# main.net
KiCad netlist of a schematic drawn in EAGLE
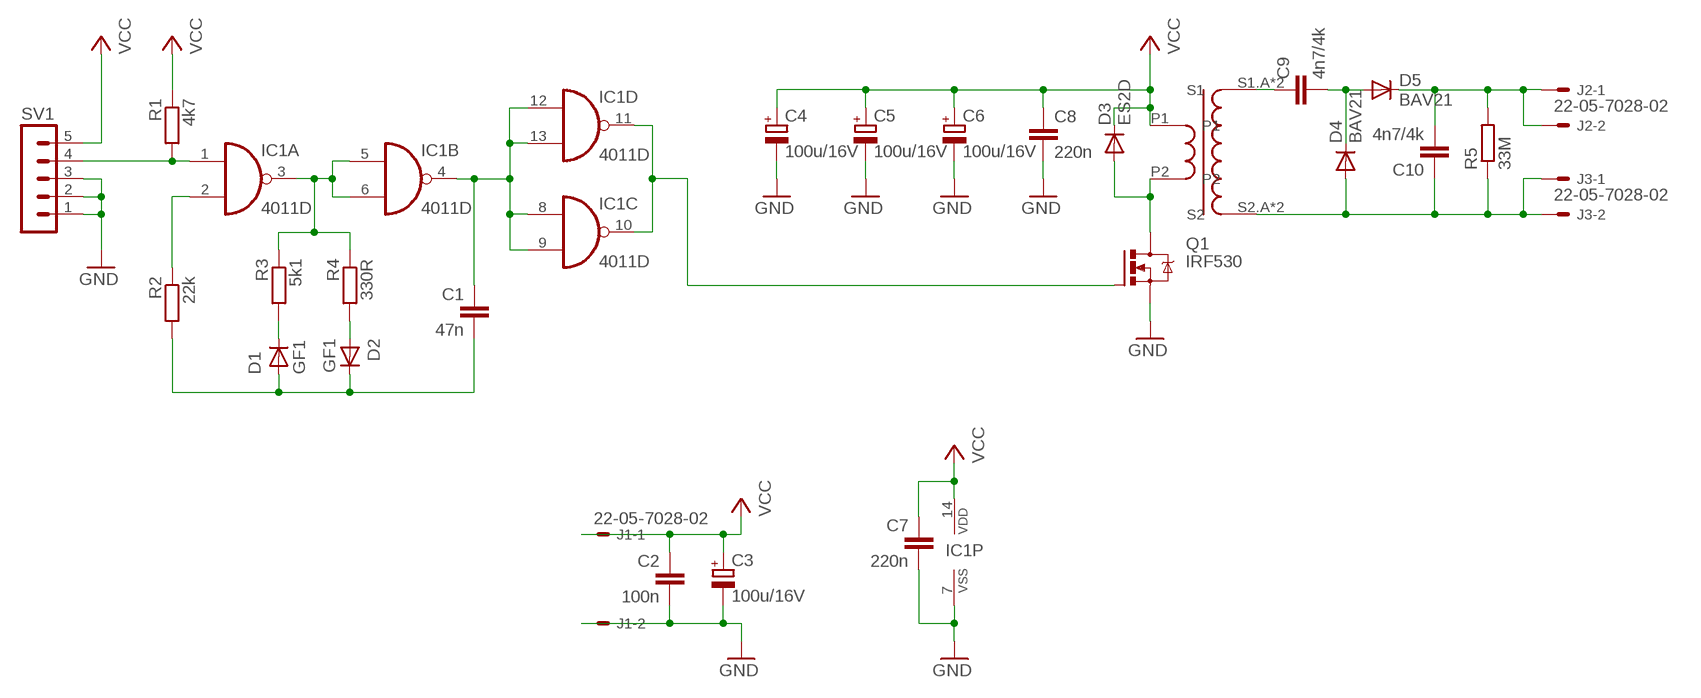
[diagram p0: schematic, sheet 1]

(export (version "E")
  (design (tool "Eeschema 10.0.6"))
  (components
    (comp (ref "11")
      (value "CCFL_INVERTER_COIL")
      (footprint "eagle-import:CCFL_INVERTER_COIL")
      (libsource (lib "eagle-import") (part "CCFL_INVERTER_COIL"))
    )
    (comp (ref "C1")
      (value "47n")
      (footprint "eagle-import:C025-025X050")
      (libsource (lib "eagle-import") (part "resistor_C-EU025-025X050"))
    )
    (comp (ref "C2")
      (value "100n")
      (footprint "eagle-import:C0805")
      (libsource (lib "eagle-import") (part "resistor_C-EUC0805"))
    )
    (comp (ref "C3")
      (value "100u/16V")
      (footprint "eagle-import:153CLV-0505")
      (libsource (lib "eagle-import") (part "CPOL-EU153CLV-0505"))
    )
    (comp (ref "C4")
      (value "100u/16V")
      (footprint "eagle-import:153CLV-0505")
      (libsource (lib "eagle-import") (part "CPOL-EU153CLV-0505"))
    )
    (comp (ref "C5")
      (value "100u/16V")
      (footprint "eagle-import:153CLV-0505")
      (libsource (lib "eagle-import") (part "resistor_CPOL-EU153CLV-0505"))
    )
    (comp (ref "C6")
      (value "100u/16V")
      (footprint "eagle-import:153CLV-0505")
      (libsource (lib "eagle-import") (part "CPOL-EU153CLV-0505"))
    )
    (comp (ref "C7")
      (value "220n")
      (footprint "eagle-import:C0805")
      (libsource (lib "eagle-import") (part "resistor_C-EUC0805"))
    )
    (comp (ref "C8")
      (value "220n")
      (footprint "eagle-import:C0805")
      (libsource (lib "eagle-import") (part "resistor_C-EUC0805"))
    )
    (comp (ref "C9")
      (value "4n7/4k")
      (footprint "eagle-import:C075-042X103")
      (libsource (lib "eagle-import") (part "C-EU075-042X103"))
    )
    (comp (ref "C10")
      (value "4n7/4k")
      (footprint "eagle-import:C075-042X103")
      (libsource (lib "eagle-import") (part "resistor_C-EU075-042X103"))
    )
    (comp (ref "D1")
      (value "GF1")
      (footprint "eagle-import:SMA-DO214AC")
      (libsource (lib "eagle-import") (part "GF1"))
    )
    (comp (ref "D2")
      (value "GF1")
      (footprint "eagle-import:SMA-DO214AC")
      (libsource (lib "eagle-import") (part "GF1"))
    )
    (comp (ref "D3")
      (value "ES2D")
      (footprint "eagle-import:SMB")
      (libsource (lib "eagle-import") (part "ES2D"))
    )
    (comp (ref "D4")
      (value "BAV21")
      (footprint "eagle-import:DO35-10")
      (libsource (lib "eagle-import") (part "BAV21"))
    )
    (comp (ref "D5")
      (value "BAV21")
      (footprint "eagle-import:DO35-10")
      (libsource (lib "eagle-import") (part "BAV21"))
    )
    (comp (ref "IC1")
      (value "4011D")
      (footprint "eagle-import:SO14")
      (libsource (lib "eagle-import") (part "4011D"))
    )
    (comp (ref "J1")
      (value "22-05-7028-02")
      (footprint "eagle-import:7395-02")
      (libsource (lib "eagle-import") (part "22-?-0205-7028"))
    )
    (comp (ref "J2")
      (value "22-05-7028-02")
      (footprint "eagle-import:7395-02")
      (libsource (lib "eagle-import") (part "22-?-0205-7028"))
    )
    (comp (ref "J3")
      (value "22-05-7028-02")
      (footprint "eagle-import:7395-02")
      (libsource (lib "eagle-import") (part "22-?-0205-7028"))
    )
    (comp (ref "Q1")
      (value "IRF530")
      (footprint "eagle-import:TO220BV")
      (libsource (lib "eagle-import") (part "IRF530"))
    )
    (comp (ref "R1")
      (value "4k7")
      (footprint "eagle-import:M0805")
      (libsource (lib "eagle-import") (part "R-EU_M0805"))
    )
    (comp (ref "R2")
      (value "22k")
      (footprint "eagle-import:M0805")
      (libsource (lib "eagle-import") (part "R-EU_M0805"))
    )
    (comp (ref "R3")
      (value "5k1")
      (footprint "eagle-import:M0805")
      (libsource (lib "eagle-import") (part "R-EU_M0805"))
    )
    (comp (ref "R4")
      (value "330R")
      (footprint "eagle-import:M0805")
      (libsource (lib "eagle-import") (part "R-EU_M0805"))
    )
    (comp (ref "R5")
      (value "33M")
      (footprint "eagle-import:0207_10")
      (libsource (lib "eagle-import") (part "R-EU_0207/10"))
    )
    (comp (ref "SV1")
      (value "MA05-1")
      (footprint "eagle-import:MA05-1")
      (libsource (lib "eagle-import") (part "MA05-1"))
    )
  )
  (nets
    (net (code "1") (name "GND") (class "Default")
      (node (ref "C2") (pin "2") (pinfunction "2_2") (pintype "passive"))
      (node (ref "C3") (pin "-") (pinfunction "-_-") (pintype "passive"))
      (node (ref "C4") (pin "-") (pinfunction "-_-") (pintype "passive"))
      (node (ref "C5") (pin "-") (pinfunction "-_-") (pintype "passive"))
      (node (ref "C6") (pin "-") (pinfunction "-_-") (pintype "passive"))
      (node (ref "C7") (pin "2") (pinfunction "2_2") (pintype "passive"))
      (node (ref "C8") (pin "2") (pinfunction "2_2") (pintype "passive"))
      (node (ref "IC1") (pin "7") (pinfunction "VSS_7") (pintype "power_in"))
      (node (ref "J1") (pin "2") (pinfunction "S_2") (pintype "passive"))
      (node (ref "Q1") (pin "S") (pinfunction "S_S") (pintype "passive"))
      (node (ref "SV1") (pin "1") (pinfunction "1_1") (pintype "passive"))
      (node (ref "SV1") (pin "2") (pinfunction "2_2") (pintype "passive"))
      (node (ref "SV1") (pin "3") (pinfunction "3_3") (pintype "passive"))
    )
    (net (code "2") (name "Net-(11-PadP2)") (class "Default")
      (node (ref "11") (pin "P2") (pinfunction "P2_P2") (pintype "input"))
      (node (ref "D3") (pin "A") (pinfunction "A_A") (pintype "passive"))
      (node (ref "Q1") (pin "D") (pinfunction "D_D") (pintype "passive"))
    )
    (net (code "3") (name "Net-(11-S1-PadS1.A)") (class "Default")
      (node (ref "11") (pin "S1.A") (pinfunction "S1_S1.A") (pintype "output"))
      (node (ref "11") (pin "S1.B") (pinfunction "S1_S1.B") (pintype "output"))
      (node (ref "C9") (pin "1") (pinfunction "1_1") (pintype "passive"))
    )
    (net (code "4") (name "Net-(C9-Pad2)") (class "Default")
      (node (ref "C9") (pin "2") (pinfunction "2_2") (pintype "passive"))
      (node (ref "D4") (pin "C") (pinfunction "C_C") (pintype "passive"))
      (node (ref "D5") (pin "A") (pinfunction "A_A") (pintype "passive"))
    )
    (net (code "5") (name "Net-(D1-C)") (class "Default")
      (node (ref "D1") (pin "K") (pinfunction "C_K") (pintype "passive"))
      (node (ref "R3") (pin "2") (pinfunction "2_2") (pintype "passive"))
    )
    (net (code "6") (name "Net-(D2-C)") (class "Default")
      (node (ref "C1") (pin "2") (pinfunction "2_2") (pintype "passive"))
      (node (ref "D1") (pin "A") (pinfunction "A_A") (pintype "passive"))
      (node (ref "D2") (pin "K") (pinfunction "C_K") (pintype "passive"))
      (node (ref "R2") (pin "2") (pinfunction "2_2") (pintype "passive"))
    )
    (net (code "7") (name "Net-(D2-PadA)") (class "Default")
      (node (ref "D2") (pin "A") (pinfunction "A_A") (pintype "passive"))
      (node (ref "R4") (pin "2") (pinfunction "2_2") (pintype "passive"))
    )
    (net (code "8") (name "Net-(IC1A-I0)") (class "Default")
      (node (ref "IC1") (pin "1") (pinfunction "I0_1") (pintype "input"))
      (node (ref "R1") (pin "2") (pinfunction "2_2") (pintype "passive"))
      (node (ref "SV1") (pin "4") (pinfunction "4_4") (pintype "passive"))
    )
    (net (code "9") (name "Net-(IC1A-I1)") (class "Default")
      (node (ref "IC1") (pin "2") (pinfunction "I1_2") (pintype "input"))
      (node (ref "R2") (pin "1") (pinfunction "1_1") (pintype "passive"))
    )
    (net (code "10") (name "Net-(IC1A-O)") (class "Default")
      (node (ref "IC1") (pin "3") (pinfunction "O_3") (pintype "output"))
      (node (ref "IC1") (pin "5") (pinfunction "I0_5") (pintype "input"))
      (node (ref "IC1") (pin "6") (pinfunction "I1_6") (pintype "input"))
      (node (ref "R3") (pin "1") (pinfunction "1_1") (pintype "passive"))
      (node (ref "R4") (pin "1") (pinfunction "1_1") (pintype "passive"))
    )
    (net (code "11") (name "Net-(IC1B-O)") (class "Default")
      (node (ref "C1") (pin "1") (pinfunction "1_1") (pintype "passive"))
      (node (ref "IC1") (pin "12") (pinfunction "I0_12") (pintype "input"))
      (node (ref "IC1") (pin "13") (pinfunction "I1_13") (pintype "input"))
      (node (ref "IC1") (pin "4") (pinfunction "O_4") (pintype "output"))
      (node (ref "IC1") (pin "8") (pinfunction "I0_8") (pintype "input"))
      (node (ref "IC1") (pin "9") (pinfunction "I1_9") (pintype "input"))
    )
    (net (code "12") (name "Net-(IC1C-O)") (class "Default")
      (node (ref "IC1") (pin "10") (pinfunction "O_10") (pintype "output"))
      (node (ref "IC1") (pin "11") (pinfunction "O_11") (pintype "output"))
      (node (ref "Q1") (pin "G") (pinfunction "G_G") (pintype "passive"))
    )
    (net (code "13") (name "Net-(J2A-S)") (class "Default")
      (node (ref "C10") (pin "2") (pinfunction "2_2") (pintype "passive"))
      (node (ref "D5") (pin "C") (pinfunction "C_C") (pintype "passive"))
      (node (ref "J2") (pin "1") (pinfunction "S_1") (pintype "passive"))
      (node (ref "J2") (pin "2") (pinfunction "S_2") (pintype "passive"))
      (node (ref "R5") (pin "2") (pinfunction "2_2") (pintype "passive"))
    )
    (net (code "14") (name "Net-(J3A-S)") (class "Default")
      (node (ref "11") (pin "S2.A") (pinfunction "S2_S2.A") (pintype "output"))
      (node (ref "11") (pin "S2.B") (pinfunction "S2_S2.B") (pintype "output"))
      (node (ref "C10") (pin "1") (pinfunction "1_1") (pintype "passive"))
      (node (ref "D4") (pin "A") (pinfunction "A_A") (pintype "passive"))
      (node (ref "J3") (pin "1") (pinfunction "S_1") (pintype "passive"))
      (node (ref "J3") (pin "2") (pinfunction "S_2") (pintype "passive"))
      (node (ref "R5") (pin "1") (pinfunction "1_1") (pintype "passive"))
    )
    (net (code "15") (name "VCC") (class "Default")
      (node (ref "11") (pin "P1") (pinfunction "P1_P1") (pintype "input"))
      (node (ref "C2") (pin "1") (pinfunction "1_1") (pintype "passive"))
      (node (ref "C3") (pin "+") (pinfunction "+_+") (pintype "passive"))
      (node (ref "C4") (pin "+") (pinfunction "+_+") (pintype "passive"))
      (node (ref "C5") (pin "+") (pinfunction "+_+") (pintype "passive"))
      (node (ref "C6") (pin "+") (pinfunction "+_+") (pintype "passive"))
      (node (ref "C7") (pin "1") (pinfunction "1_1") (pintype "passive"))
      (node (ref "C8") (pin "1") (pinfunction "1_1") (pintype "passive"))
      (node (ref "D3") (pin "C") (pinfunction "C_C") (pintype "passive"))
      (node (ref "IC1") (pin "14") (pinfunction "VDD_14") (pintype "power_in"))
      (node (ref "J1") (pin "1") (pinfunction "S_1") (pintype "passive"))
      (node (ref "R1") (pin "1") (pinfunction "1_1") (pintype "passive"))
      (node (ref "SV1") (pin "5") (pinfunction "5_5") (pintype "passive"))
    )
  )
)
